# Display.net
KiCad netlist of a schematic drawn in Altium Designer
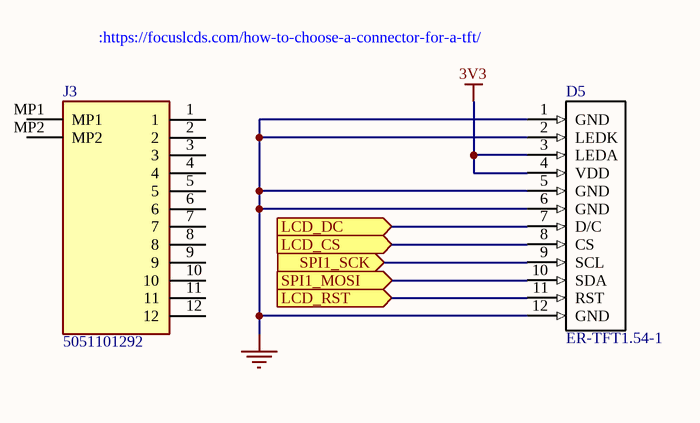
[diagram p0: Display.SchDoc]

(export (version "E")
  (design (tool "Eeschema 10.0.6"))
  (components
    (comp (ref "D5")
      (value "ER-TFT1.54-1")
      (footprint "IPS 1.54 inches")
      (description "IPS display 1.54 inch SPI")
      (libsource (lib "MISC") (part "IPS 1.54 inch"))
    )
    (comp (ref "J3")
      (value "5051101292")
      (footprint "5051101292")
      (description "CONN FPC BOTTOM 12POS .5MM R/A")
      (libsource (lib "Tese_SymbolLib") (part "5051101292"))
    )
  )
  (nets
    (net (code "1") (name "/LCD_CS") (class "Default")
      (node (ref "D5") (pin "8") (pinfunction "CS_8") (pintype "input"))
    )
    (net (code "2") (name "/LCD_DC") (class "Default")
      (node (ref "D5") (pin "7") (pinfunction "D/C_7") (pintype "input"))
    )
    (net (code "3") (name "/LCD_RST") (class "Default")
      (node (ref "D5") (pin "11") (pinfunction "RST_11") (pintype "input"))
    )
    (net (code "4") (name "/SPI1_MOSI") (class "Default")
      (node (ref "D5") (pin "10") (pinfunction "SDA_10") (pintype "input"))
    )
    (net (code "5") (name "/SPI1_SCK") (class "Default")
      (node (ref "D5") (pin "9") (pinfunction "SCL_9") (pintype "input"))
    )
    (net (code "6") (name "3V3") (class "Default")
      (node (ref "D5") (pin "3") (pinfunction "LEDA_3") (pintype "input"))
      (node (ref "D5") (pin "4") (pinfunction "VDD_4") (pintype "input"))
    )
    (net (code "7") (name "GND") (class "Default")
      (node (ref "D5") (pin "1") (pinfunction "GND_1") (pintype "input"))
      (node (ref "D5") (pin "12") (pinfunction "GND_12") (pintype "input"))
      (node (ref "D5") (pin "2") (pinfunction "LEDK_2") (pintype "input"))
      (node (ref "D5") (pin "5") (pinfunction "GND_5") (pintype "input"))
      (node (ref "D5") (pin "6") (pinfunction "GND_6") (pintype "input"))
    )
    (net (code "8") (name "unconnected-(J3-Pad1)") (class "Default")
      (node (ref "J3") (pin "1") (pinfunction "1_1") (pintype "passive"))
    )
    (net (code "9") (name "unconnected-(J3-Pad2)") (class "Default")
      (node (ref "J3") (pin "2") (pinfunction "2_2") (pintype "passive"))
    )
    (net (code "10") (name "unconnected-(J3-Pad3)") (class "Default")
      (node (ref "J3") (pin "3") (pinfunction "3_3") (pintype "passive"))
    )
    (net (code "11") (name "unconnected-(J3-Pad4)") (class "Default")
      (node (ref "J3") (pin "4") (pinfunction "4_4") (pintype "passive"))
    )
    (net (code "12") (name "unconnected-(J3-Pad5)") (class "Default")
      (node (ref "J3") (pin "5") (pinfunction "5_5") (pintype "passive"))
    )
    (net (code "13") (name "unconnected-(J3-Pad6)") (class "Default")
      (node (ref "J3") (pin "6") (pinfunction "6_6") (pintype "passive"))
    )
    (net (code "14") (name "unconnected-(J3-Pad7)") (class "Default")
      (node (ref "J3") (pin "7") (pinfunction "7_7") (pintype "passive"))
    )
    (net (code "15") (name "unconnected-(J3-Pad8)") (class "Default")
      (node (ref "J3") (pin "8") (pinfunction "8_8") (pintype "passive"))
    )
    (net (code "16") (name "unconnected-(J3-Pad9)") (class "Default")
      (node (ref "J3") (pin "9") (pinfunction "9_9") (pintype "passive"))
    )
    (net (code "17") (name "unconnected-(J3-Pad10)") (class "Default")
      (node (ref "J3") (pin "10") (pinfunction "10_10") (pintype "passive"))
    )
    (net (code "18") (name "unconnected-(J3-Pad11)") (class "Default")
      (node (ref "J3") (pin "11") (pinfunction "11_11") (pintype "passive"))
    )
    (net (code "19") (name "unconnected-(J3-Pad12)") (class "Default")
      (node (ref "J3") (pin "12") (pinfunction "12_12") (pintype "passive"))
    )
    (net (code "20") (name "unconnected-(J3-PadMP1)") (class "Default")
      (node (ref "J3") (pin "MP1") (pinfunction "MP1_MP1") (pintype "passive"))
    )
    (net (code "21") (name "unconnected-(J3-PadMP2)") (class "Default")
      (node (ref "J3") (pin "MP2") (pinfunction "MP2_MP2") (pintype "passive"))
    )
  )
)
